# FRONT-UNIT.net
KiCad netlist of a schematic drawn in Altium Designer
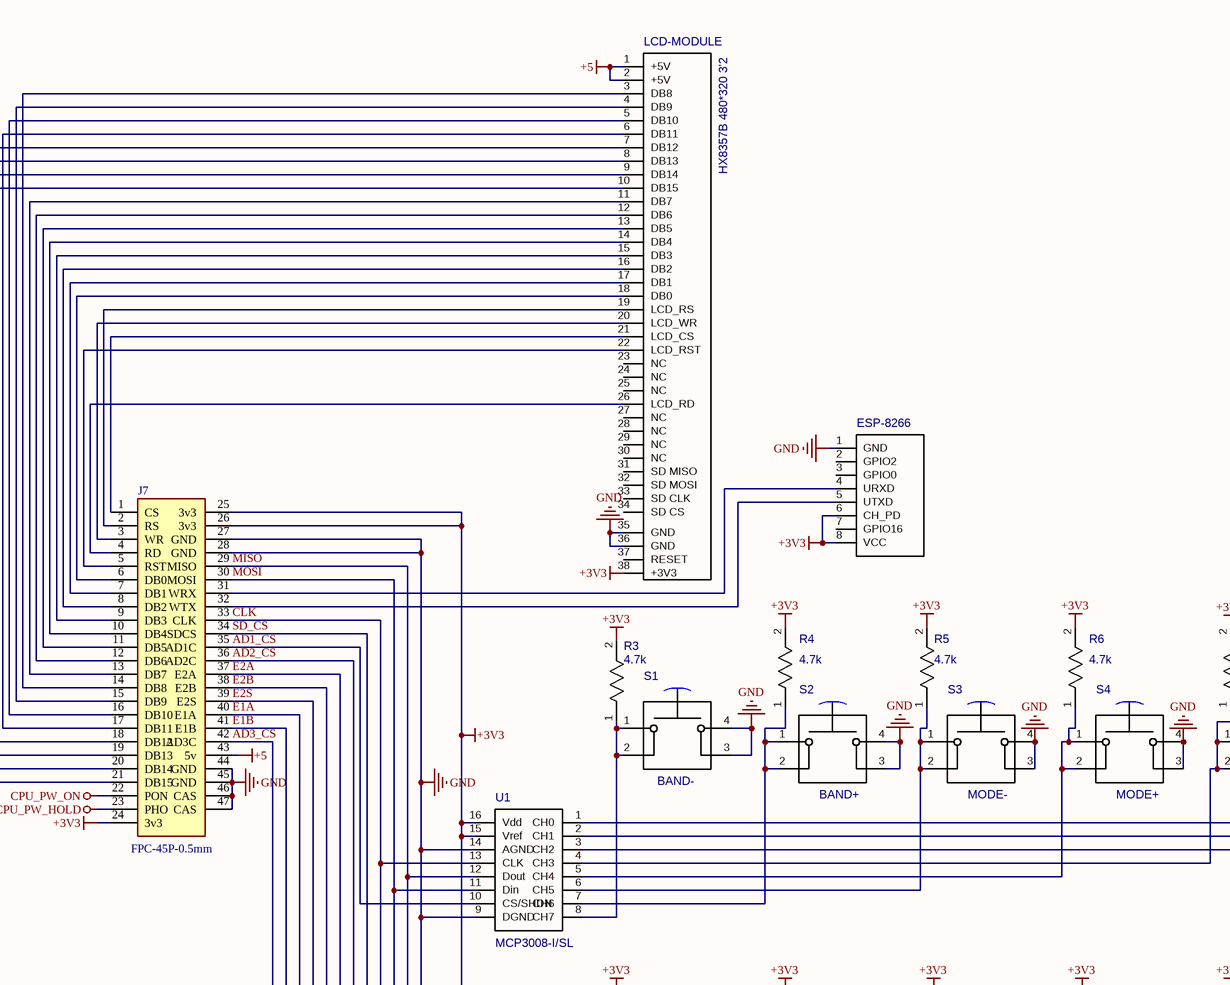
[diagram p0: FRONT-UNIT.SchDoc, top left]
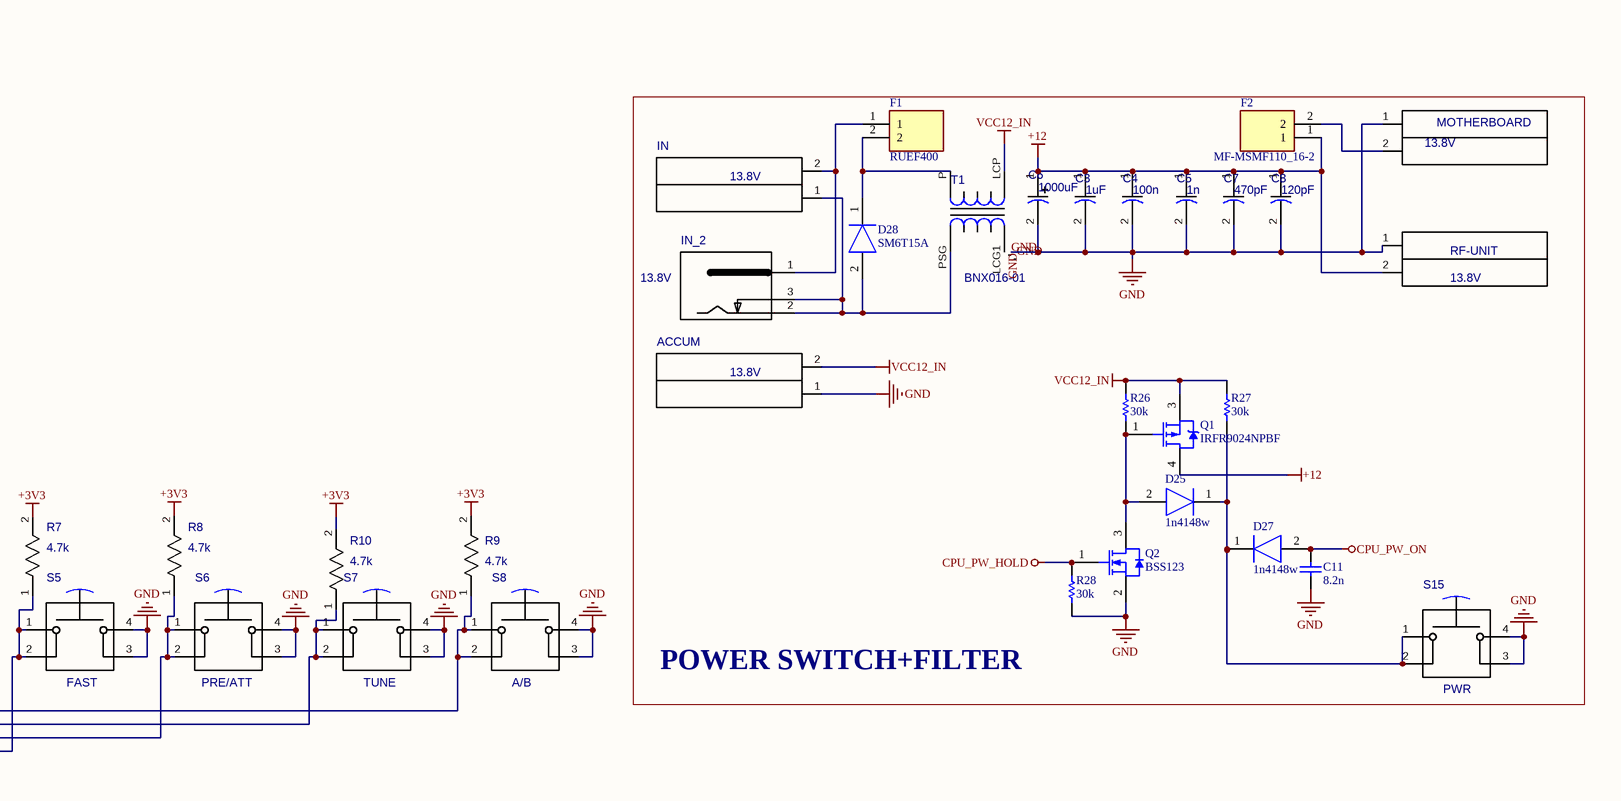
[diagram p1: FRONT-UNIT.SchDoc, top right]
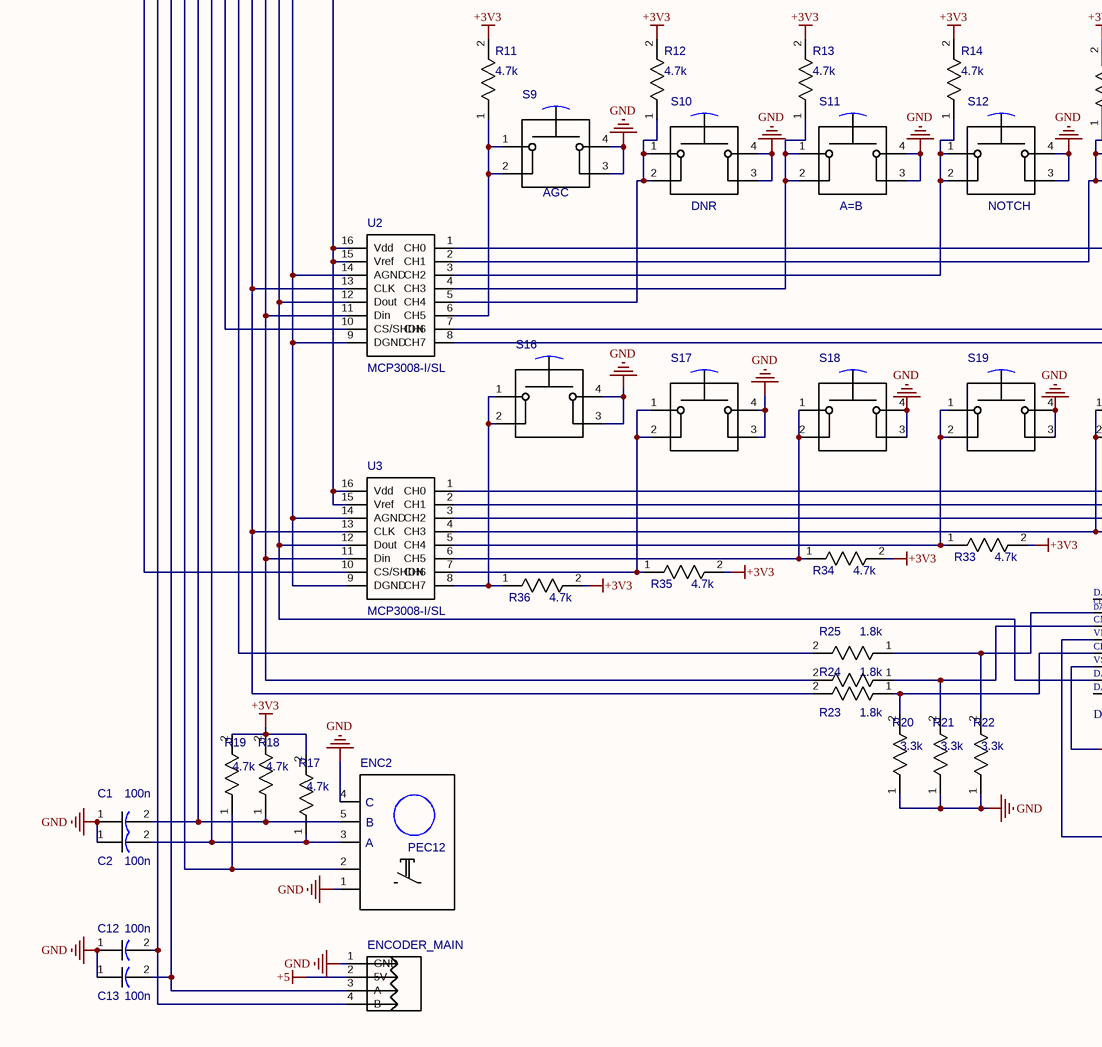
[diagram p2: FRONT-UNIT.SchDoc, bottom left]
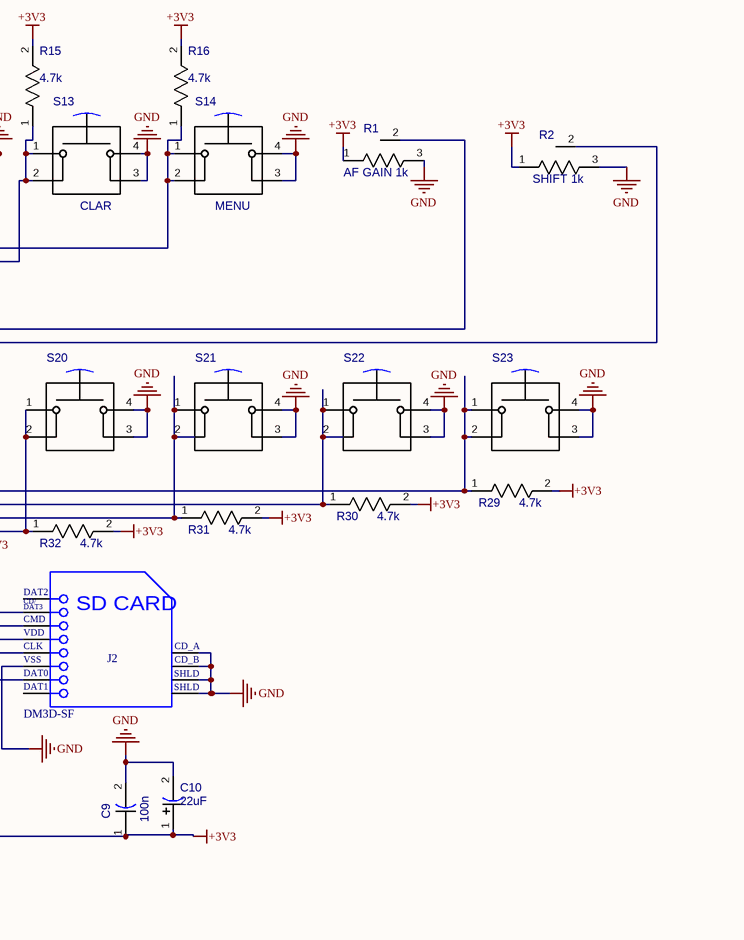
[diagram p3: FRONT-UNIT.SchDoc, bottom right]

(export (version "E")
  (design (tool "Eeschema 10.0.6"))
  (components
    (comp (ref "ACCUM")
      (value "13.8V")
      (footprint "JX2")
      (description "JX2")
      (libsource (lib "*") (part "JX2"))
    )
    (comp (ref "C1")
      (value "100n")
      (footprint "CAP_0805")
      (description "CAP_0805")
      (libsource (lib "*") (part "CAP_0805"))
    )
    (comp (ref "C2")
      (value "100n")
      (footprint "CAP_0805")
      (description "CAP_0805")
      (libsource (lib "*") (part "CAP_0805"))
    )
    (comp (ref "C3")
      (value "1uF")
      (footprint "CAP_1206")
      (description "CAP_1206")
      (libsource (lib "*") (part "CAP_1206"))
    )
    (comp (ref "C4")
      (value "100n")
      (footprint "CAP_1206")
      (description "CAP_1206")
      (libsource (lib "*") (part "CAP_1206"))
    )
    (comp (ref "C5")
      (value "1n")
      (footprint "CAP_1206")
      (description "CAP_1206")
      (libsource (lib "*") (part "CAP_1206"))
    )
    (comp (ref "C6")
      (value "1000uF")
      (footprint "CAP250RP")
      (description "CAP250RP")
      (libsource (lib "*") (part "CAP250RP"))
    )
    (comp (ref "C7")
      (value "470pF")
      (footprint "CAP_1206")
      (description "CAP_1206")
      (libsource (lib "*") (part "CAP_1206"))
    )
    (comp (ref "C8")
      (value "120pF")
      (footprint "CAP_1206")
      (description "CAP_1206")
      (libsource (lib "*") (part "CAP_1206"))
    )
    (comp (ref "C9")
      (value "100n")
      (footprint "CAP_0805")
      (description "CAP_0805")
      (libsource (lib "*") (part "CAP_0805"))
    )
    (comp (ref "C10")
      (value "22uF")
      (footprint "EEEFC_sizeB")
      (description "EEEFC_sizeB")
      (libsource (lib "*") (part "EEEFC_sizeB"))
    )
    (comp (ref "C11")
      (value "8.2n")
      (footprint "CAPC2013X94X50LL20T25")
      (description "CAP_1206")
      (fields
        (field (name "MANUFACTURER") "AVX Interconnect / Elco")
        (field (name "PART NUMBER") "08055C822KAT2A")
      )
      (libsource (lib "Altium Content Vault") (part "CAP"))
    )
    (comp (ref "C12")
      (value "100n")
      (footprint "CAP_0805")
      (description "CAP_0805")
      (libsource (lib "*") (part "CAP_0805"))
    )
    (comp (ref "C13")
      (value "100n")
      (footprint "CAP_0805")
      (description "CAP_0805")
      (libsource (lib "*") (part "CAP_0805"))
    )
    (comp (ref "D25")
      (value "1n4148w")
      (footprint "SamacSys:SOD3716X135N")
      (description "Diode")
      (libsource (lib "*") (part "1n4148w"))
    )
    (comp (ref "D27")
      (value "1n4148w")
      (footprint "SamacSys:SOD3716X135N")
      (description "Diode")
      (libsource (lib "*") (part "1n4148w"))
    )
    (comp (ref "D28")
      (value "SM6T15A")
      (footprint "SamacSys:SMBJ36CATR")
      (description "Diode")
      (fields (field (name "MOUSER PART NUMBER") "511-SM6T15A") (field (name "RS PART NUMBER") "4864915P"))
      (libsource (lib "*") (part "SM6T15A"))
    )
    (comp (ref "ENC2") (value "PEC12") (footprint "PEC12") (libsource (lib "*") (part "PEC12")))
    (comp (ref "ENCODER_MAIN")
      (value "OPTICAL ENCODER")
      (footprint "644456-4")
      (libsource (lib "*") (part "644456-4"))
    )
    (comp (ref "ESP-8266")
      (value "ESP-01 ESP8266")
      (footprint "ESP-01 ESP8266")
      (libsource (lib "*") (part "ESP-01 ESP8266"))
    )
    (comp (ref "F1")
      (value "RUEF400")
      (footprint "SamacSys:RUEF400")
      (description "Fuse")
      (fields (field (name "MOUSER PART NUMBER") "650-RUEF400") (field (name "RS PART NUMBER") "5176837P"))
      (libsource (lib "*") (part "RUEF400"))
    )
    (comp (ref "F2")
      (value "MF-MSMF110_16-2")
      (footprint "SamacSys:FUSC4632X85N")
      (description "Fuse")
      (fields
        (field (name "MANUFACTURER_PART_NUMBER") "MF-MSMF110/16-2")
        (field (name "MOUSER PART NUMBER") "652-MF-MSMF110/16-2")
      )
      (libsource (lib "*") (part "MF-MSMF110_16-2"))
    )
    (comp (ref "IN") (value "13.8V") (footprint "JX2") (description "JX2") (libsource (lib "*") (part "JX2")))
    (comp (ref "IN_2")
      (value "13.8V")
      (footprint "PJ-050B")
      (description "PJ-050B")
      (libsource (lib "*") (part "PJ-050B"))
    )
    (comp (ref "J2")
      (value "DM3D-SF")
      (footprint "HIRO-DM3D-SF_V")
      (fields (field (name "MANUFACTURER") "Hirose Electric"))
      (libsource (lib "Altium Content Vault") (part "CN-SD-8-2SW-2S"))
    )
    (comp (ref "J7")
      (value "FPC-45P-0.5mm")
      (footprint "SamacSys:FH12S45S05SH60")
      (description "Connector")
      (fields
        (field (name "MANUFACTURER_PART_NUMBER") "FH12S-45S-0.5SH(55)")
        (field (name "MOUSER PART NUMBER") "798-FH12S-45S-05SH55")
      )
      (libsource (lib "*") (part "FH12S-45S-0.5SH_55_"))
    )
    (comp (ref "LCD-MODULE")
      (value "HX8357B 480*320 3'2")
      (footprint "LCD-MODULE-3.2-480-320")
      (description "LCD-MODULE_3'2_480х320")
      (libsource (lib "FRONT-UNIT") (part "LCD-MODULE_3'2_480х320"))
    )
    (comp (ref "MOTHERBOARD")
      (value "13.8V")
      (footprint "JX2")
      (description "JX2")
      (libsource (lib "*") (part "JX2"))
    )
    (comp (ref "Q1")
      (value "IRFR9024NPBF")
      (footprint "ONSC-DPAK-3-369C-01_V")
      (description "IRFR9024NPBF, Транзистор, Р-канал 55В 11А")
      (fields (field (name "MANUFACTURER") "On Semiconductor") (field (name "PARTNUMBER") "NTD2955G"))
      (libsource (lib "Altium Content Vault") (part "ONSC-PMOS-G1S3D4-3_B"))
    )
    (comp (ref "Q2")
      (value "BSS123")
      (footprint "FAIR-SOT23-3_V")
      (fields (field (name "MANUFACTURER") "Fairchild"))
      (libsource (lib "Altium Content Vault") (part "NEMOS-GSD-3"))
    )
    (comp (ref "R1")
      (value "AF GAIN 1k")
      (footprint "PTV09")
      (description "Adjustable Resistor PTV09")
      (fields (field (name "Comment") "ptv09a-4225f-b102"))
      (libsource (lib "*") (part "PTV09"))
    )
    (comp (ref "R2")
      (value "SHIFT 1k")
      (footprint "PTV09")
      (description "Adjustable Resistor PTV09")
      (fields (field (name "Comment") "ptv09a-4225f-b102"))
      (libsource (lib "*") (part "PTV09"))
    )
    (comp (ref "R3")
      (value "4.7k")
      (footprint "RES_0805")
      (description "RES_0805")
      (libsource (lib "*") (part "RES_0805"))
    )
    (comp (ref "R4")
      (value "4.7k")
      (footprint "RES_0805")
      (description "RES_0805")
      (libsource (lib "*") (part "RES_0805"))
    )
    (comp (ref "R5")
      (value "4.7k")
      (footprint "RES_0805")
      (description "RES_0805")
      (libsource (lib "*") (part "RES_0805"))
    )
    (comp (ref "R6")
      (value "4.7k")
      (footprint "RES_0805")
      (description "RES_0805")
      (libsource (lib "*") (part "RES_0805"))
    )
    (comp (ref "R7")
      (value "4.7k")
      (footprint "RES_0805")
      (description "RES_0805")
      (libsource (lib "*") (part "RES_0805"))
    )
    (comp (ref "R8")
      (value "4.7k")
      (footprint "RES_0805")
      (description "RES_0805")
      (libsource (lib "*") (part "RES_0805"))
    )
    (comp (ref "R9")
      (value "4.7k")
      (footprint "RES_0805")
      (description "RES_0805")
      (libsource (lib "*") (part "RES_0805"))
    )
    (comp (ref "R10")
      (value "4.7k")
      (footprint "RES_0805")
      (description "RES_0805")
      (libsource (lib "*") (part "RES_0805"))
    )
    (comp (ref "R11")
      (value "4.7k")
      (footprint "RES_0805")
      (description "RES_0805")
      (libsource (lib "*") (part "RES_0805"))
    )
    (comp (ref "R12")
      (value "4.7k")
      (footprint "RES_0805")
      (description "RES_0805")
      (libsource (lib "*") (part "RES_0805"))
    )
    (comp (ref "R13")
      (value "4.7k")
      (footprint "RES_0805")
      (description "RES_0805")
      (libsource (lib "*") (part "RES_0805"))
    )
    (comp (ref "R14")
      (value "4.7k")
      (footprint "RES_0805")
      (description "RES_0805")
      (libsource (lib "*") (part "RES_0805"))
    )
    (comp (ref "R15")
      (value "4.7k")
      (footprint "RES_0805")
      (description "RES_0805")
      (libsource (lib "*") (part "RES_0805"))
    )
    (comp (ref "R16")
      (value "4.7k")
      (footprint "RES_0805")
      (description "RES_0805")
      (libsource (lib "*") (part "RES_0805"))
    )
    (comp (ref "R17")
      (value "4.7k")
      (footprint "RES_0805")
      (description "RES_0805")
      (libsource (lib "*") (part "RES_0805"))
    )
    (comp (ref "R18")
      (value "4.7k")
      (footprint "RES_0805")
      (description "RES_0805")
      (libsource (lib "*") (part "RES_0805"))
    )
    (comp (ref "R19")
      (value "4.7k")
      (footprint "RES_0805")
      (description "RES_0805")
      (libsource (lib "*") (part "RES_0805"))
    )
    (comp (ref "R20")
      (value "3.3k")
      (footprint "RES_0805")
      (description "RES_0805")
      (libsource (lib "*") (part "RES_0805"))
    )
    (comp (ref "R21")
      (value "3.3k")
      (footprint "RES_0805")
      (description "RES_0805")
      (libsource (lib "*") (part "RES_0805"))
    )
    (comp (ref "R22")
      (value "3.3k")
      (footprint "RES_0805")
      (description "RES_0805")
      (libsource (lib "*") (part "RES_0805"))
    )
    (comp (ref "R23")
      (value "1.8k")
      (footprint "RES_0805")
      (description "RES_0805")
      (libsource (lib "*") (part "RES_0805"))
    )
    (comp (ref "R24")
      (value "1.8k")
      (footprint "RES_0805")
      (description "RES_0805")
      (libsource (lib "*") (part "RES_0805"))
    )
    (comp (ref "R25")
      (value "1.8k")
      (footprint "RES_0805")
      (description "RES_0805")
      (libsource (lib "*") (part "RES_0805"))
    )
    (comp (ref "R26")
      (value "30k")
      (footprint "RESC2013X60X40NL20T25")
      (description "RES_0805")
      (fields (field (name "MANUFACTURER") "Panasonic") (field (name "PART NUMBER") "ERA-6AEB303V"))
      (libsource (lib "Altium Content Vault") (part "RES"))
    )
    (comp (ref "R27")
      (value "30k")
      (footprint "RESC2013X60X40NL20T25")
      (description "RES_0805")
      (fields (field (name "MANUFACTURER") "Panasonic") (field (name "PART NUMBER") "ERA-6AEB303V"))
      (libsource (lib "Altium Content Vault") (part "RES"))
    )
    (comp (ref "R28")
      (value "30k")
      (footprint "RESC2013X60X40NL20T25")
      (description "RES_0805")
      (fields (field (name "MANUFACTURER") "Panasonic") (field (name "PART NUMBER") "ERA-6AEB303V"))
      (libsource (lib "Altium Content Vault") (part "RES"))
    )
    (comp (ref "R29")
      (value "4.7k")
      (footprint "RES_0805")
      (description "RES_0805")
      (libsource (lib "*") (part "RES_0805"))
    )
    (comp (ref "R30")
      (value "4.7k")
      (footprint "RES_0805")
      (description "RES_0805")
      (libsource (lib "*") (part "RES_0805"))
    )
    (comp (ref "R31")
      (value "4.7k")
      (footprint "RES_0805")
      (description "RES_0805")
      (libsource (lib "*") (part "RES_0805"))
    )
    (comp (ref "R32")
      (value "4.7k")
      (footprint "RES_0805")
      (description "RES_0805")
      (libsource (lib "*") (part "RES_0805"))
    )
    (comp (ref "R33")
      (value "4.7k")
      (footprint "RES_0805")
      (description "RES_0805")
      (libsource (lib "*") (part "RES_0805"))
    )
    (comp (ref "R34")
      (value "4.7k")
      (footprint "RES_0805")
      (description "RES_0805")
      (libsource (lib "*") (part "RES_0805"))
    )
    (comp (ref "R35")
      (value "4.7k")
      (footprint "RES_0805")
      (description "RES_0805")
      (libsource (lib "*") (part "RES_0805"))
    )
    (comp (ref "R36")
      (value "4.7k")
      (footprint "RES_0805")
      (description "RES_0805")
      (libsource (lib "*") (part "RES_0805"))
    )
    (comp (ref "RF-UNIT")
      (value "13.8V")
      (footprint "JX2")
      (description "JX2")
      (libsource (lib "*") (part "JX2"))
    )
    (comp (ref "S1")
      (value "BAND-")
      (footprint "PTS645SK50LFS")
      (description "PTS645SK50LFS")
      (libsource (lib "*") (part "PTS645SK50LFS"))
    )
    (comp (ref "S2")
      (value "BAND+")
      (footprint "PTS645SK50LFS")
      (description "PTS645SK50LFS")
      (libsource (lib "*") (part "PTS645SK50LFS"))
    )
    (comp (ref "S3")
      (value "MODE-")
      (footprint "PTS645SK50LFS")
      (description "PTS645SK50LFS")
      (libsource (lib "*") (part "PTS645SK50LFS"))
    )
    (comp (ref "S4")
      (value "MODE+")
      (footprint "PTS645SK50LFS")
      (description "PTS645SK50LFS")
      (libsource (lib "*") (part "PTS645SK50LFS"))
    )
    (comp (ref "S5")
      (value "FAST")
      (footprint "PTS645SK50LFS")
      (description "PTS645SK50LFS")
      (libsource (lib "*") (part "PTS645SK50LFS"))
    )
    (comp (ref "S6")
      (value "PRE/ATT")
      (footprint "PTS645SK50LFS")
      (description "PTS645SK50LFS")
      (libsource (lib "*") (part "PTS645SK50LFS"))
    )
    (comp (ref "S7")
      (value "TUNE")
      (footprint "PTS645SK50LFS")
      (description "PTS645SK50LFS")
      (libsource (lib "*") (part "PTS645SK50LFS"))
    )
    (comp (ref "S8")
      (value "A/B")
      (footprint "PTS645SK50LFS")
      (description "PTS645SK50LFS")
      (libsource (lib "*") (part "PTS645SK50LFS"))
    )
    (comp (ref "S9")
      (value "AGC")
      (footprint "PTS645SK50LFS")
      (description "PTS645SK50LFS")
      (libsource (lib "*") (part "PTS645SK50LFS"))
    )
    (comp (ref "S10")
      (value "DNR")
      (footprint "PTS645SK50LFS")
      (description "PTS645SK50LFS")
      (libsource (lib "*") (part "PTS645SK50LFS"))
    )
    (comp (ref "S11")
      (value "A=B")
      (footprint "PTS645SK50LFS")
      (description "PTS645SK50LFS")
      (libsource (lib "*") (part "PTS645SK50LFS"))
    )
    (comp (ref "S12")
      (value "NOTCH")
      (footprint "PTS645SK50LFS")
      (description "PTS645SK50LFS")
      (libsource (lib "*") (part "PTS645SK50LFS"))
    )
    (comp (ref "S13")
      (value "CLAR")
      (footprint "PTS645SK50LFS")
      (description "PTS645SK50LFS")
      (libsource (lib "*") (part "PTS645SK50LFS"))
    )
    (comp (ref "S14")
      (value "MENU")
      (footprint "PTS645SK50LFS")
      (description "PTS645SK50LFS")
      (libsource (lib "*") (part "PTS645SK50LFS"))
    )
    (comp (ref "S15")
      (value "PWR")
      (footprint "PTS645SK50LFS")
      (description "PTS645SK50LFS")
      (libsource (lib "*") (part "PTS645SK50LFS"))
    )
    (comp (ref "S16")
      (value "PTS645SK50LFS")
      (footprint "PTS645SK50LFS")
      (libsource (lib "*") (part "PTS645SK50LFS"))
    )
    (comp (ref "S17")
      (value "PTS645SK50LFS")
      (footprint "PTS645SK50LFS")
      (libsource (lib "*") (part "PTS645SK50LFS"))
    )
    (comp (ref "S18")
      (value "PTS645SK50LFS")
      (footprint "PTS645SK50LFS")
      (libsource (lib "*") (part "PTS645SK50LFS"))
    )
    (comp (ref "S19")
      (value "PTS645SK50LFS")
      (footprint "PTS645SK50LFS")
      (libsource (lib "*") (part "PTS645SK50LFS"))
    )
    (comp (ref "S20")
      (value "PTS645SK50LFS")
      (footprint "PTS645SK50LFS")
      (libsource (lib "*") (part "PTS645SK50LFS"))
    )
    (comp (ref "S21")
      (value "PTS645SK50LFS")
      (footprint "PTS645SK50LFS")
      (libsource (lib "*") (part "PTS645SK50LFS"))
    )
    (comp (ref "S22")
      (value "PTS645SK50LFS")
      (footprint "PTS645SK50LFS")
      (libsource (lib "*") (part "PTS645SK50LFS"))
    )
    (comp (ref "S23")
      (value "PTS645SK50LFS")
      (footprint "PTS645SK50LFS")
      (libsource (lib "*") (part "PTS645SK50LFS"))
    )
    (comp (ref "T1")
      (value "BNX016-01")
      (footprint "TRANSF_ICORE")
      (libsource (lib "*") (part "TRANSF_ICORE"))
    )
    (comp (ref "U1")
      (value "MCP3008-I/SL")
      (footprint "MCP3008-I/SL")
      (libsource (lib "*") (part "MCP3008-I/SL"))
    )
    (comp (ref "U2")
      (value "MCP3008-I/SL")
      (footprint "MCP3008-I/SL")
      (libsource (lib "*") (part "MCP3008-I/SL"))
    )
    (comp (ref "U3")
      (value "MCP3008-I/SL")
      (footprint "MCP3008-I/SL")
      (libsource (lib "*") (part "MCP3008-I/SL"))
    )
  )
  (nets
    (net (code "1") (name "+3V3") (class "Default")
      (node (ref "C10") (pin "1") (pinfunction "PLUS_1") (pintype "passive"))
      (node (ref "C9") (pin "1") (pinfunction "1_1") (pintype "passive"))
      (node (ref "ESP-8266") (pin "6") (pinfunction "CH_PD_6") (pintype "passive"))
      (node (ref "ESP-8266") (pin "8") (pinfunction "VCC_8") (pintype "passive"))
      (node (ref "J2") (pin "4") (pinfunction "VDD_4") (pintype "passive"))
      (node (ref "J7") (pin "24") (pinfunction "3v3_24") (pintype "passive"))
      (node (ref "J7") (pin "25") (pinfunction "3v3_25") (pintype "passive"))
      (node (ref "J7") (pin "26") (pinfunction "3v3_26") (pintype "passive"))
      (node (ref "LCD-MODULE") (pin "38") (pinfunction "+3V3_38") (pintype "passive"))
      (node (ref "R1") (pin "1") (pinfunction "CW_1") (pintype "passive"))
      (node (ref "R10") (pin "2") (pinfunction "2_2") (pintype "passive"))
      (node (ref "R11") (pin "2") (pinfunction "2_2") (pintype "passive"))
      (node (ref "R12") (pin "2") (pinfunction "2_2") (pintype "passive"))
      (node (ref "R13") (pin "2") (pinfunction "2_2") (pintype "passive"))
      (node (ref "R14") (pin "2") (pinfunction "2_2") (pintype "passive"))
      (node (ref "R15") (pin "2") (pinfunction "2_2") (pintype "passive"))
      (node (ref "R16") (pin "2") (pinfunction "2_2") (pintype "passive"))
      (node (ref "R17") (pin "2") (pinfunction "2_2") (pintype "passive"))
      (node (ref "R18") (pin "2") (pinfunction "2_2") (pintype "passive"))
      (node (ref "R19") (pin "2") (pinfunction "2_2") (pintype "passive"))
      (node (ref "R2") (pin "1") (pinfunction "CW_1") (pintype "passive"))
      (node (ref "R29") (pin "2") (pinfunction "2_2") (pintype "passive"))
      (node (ref "R3") (pin "2") (pinfunction "2_2") (pintype "passive"))
      (node (ref "R30") (pin "2") (pinfunction "2_2") (pintype "passive"))
      (node (ref "R31") (pin "2") (pinfunction "2_2") (pintype "passive"))
      (node (ref "R32") (pin "2") (pinfunction "2_2") (pintype "passive"))
      (node (ref "R33") (pin "2") (pinfunction "2_2") (pintype "passive"))
      (node (ref "R34") (pin "2") (pinfunction "2_2") (pintype "passive"))
      (node (ref "R35") (pin "2") (pinfunction "2_2") (pintype "passive"))
      (node (ref "R36") (pin "2") (pinfunction "2_2") (pintype "passive"))
      (node (ref "R4") (pin "2") (pinfunction "2_2") (pintype "passive"))
      (node (ref "R5") (pin "2") (pinfunction "2_2") (pintype "passive"))
      (node (ref "R6") (pin "2") (pinfunction "2_2") (pintype "passive"))
      (node (ref "R7") (pin "2") (pinfunction "2_2") (pintype "passive"))
      (node (ref "R8") (pin "2") (pinfunction "2_2") (pintype "passive"))
      (node (ref "R9") (pin "2") (pinfunction "2_2") (pintype "passive"))
      (node (ref "U1") (pin "15") (pinfunction "Vref_15") (pintype "passive"))
      (node (ref "U1") (pin "16") (pinfunction "Vdd_16") (pintype "passive"))
      (node (ref "U2") (pin "15") (pinfunction "Vref_15") (pintype "passive"))
      (node (ref "U2") (pin "16") (pinfunction "Vdd_16") (pintype "passive"))
      (node (ref "U3") (pin "15") (pinfunction "Vref_15") (pintype "passive"))
      (node (ref "U3") (pin "16") (pinfunction "Vdd_16") (pintype "passive"))
    )
    (net (code "2") (name "+5") (class "Default")
      (node (ref "ENCODER_MAIN") (pin "2") (pinfunction "5V_2") (pintype "passive"))
      (node (ref "J7") (pin "43") (pinfunction "5v_43") (pintype "passive"))
      (node (ref "LCD-MODULE") (pin "1") (pinfunction "+5V_1") (pintype "passive"))
      (node (ref "LCD-MODULE") (pin "2") (pinfunction "+5V_2") (pintype "passive"))
    )
    (net (code "3") (name "+12") (class "Default")
      (node (ref "C3") (pin "1") (pinfunction "1_1") (pintype "passive"))
      (node (ref "C4") (pin "1") (pinfunction "1_1") (pintype "passive"))
      (node (ref "C5") (pin "1") (pinfunction "1_1") (pintype "passive"))
      (node (ref "C6") (pin "1") (pinfunction "PLUS_1") (pintype "passive"))
      (node (ref "C7") (pin "1") (pinfunction "1_1") (pintype "passive"))
      (node (ref "C8") (pin "1") (pinfunction "1_1") (pintype "passive"))
      (node (ref "F2") (pin "1") (pinfunction "1_1") (pintype "passive"))
      (node (ref "Q1") (pin "4") (pinfunction "D_4") (pintype "passive"))
      (node (ref "RF-UNIT") (pin "2") (pinfunction "1_2") (pintype "passive"))
    )
    (net (code "4") (name "/AD1_CS") (class "Default")
      (node (ref "J7") (pin "35") (pinfunction "AD1C_35") (pintype "passive"))
      (node (ref "U1") (pin "10") (pinfunction "CS/SHDN_10") (pintype "passive"))
    )
    (net (code "5") (name "/AD2_CS") (class "Default")
      (node (ref "J7") (pin "36") (pinfunction "AD2C_36") (pintype "passive"))
      (node (ref "U2") (pin "10") (pinfunction "CS/SHDN_10") (pintype "passive"))
    )
    (net (code "6") (name "/AD3_CS") (class "Default")
      (node (ref "J7") (pin "42") (pinfunction "AD3C_42") (pintype "passive"))
      (node (ref "U3") (pin "10") (pinfunction "CS/SHDN_10") (pintype "passive"))
    )
    (net (code "7") (name "/CLK") (class "Default")
      (node (ref "J7") (pin "33") (pinfunction "CLK_33") (pintype "passive"))
      (node (ref "R23") (pin "2") (pinfunction "2_2") (pintype "passive"))
      (node (ref "U1") (pin "13") (pinfunction "CLK_13") (pintype "passive"))
      (node (ref "U2") (pin "13") (pinfunction "CLK_13") (pintype "passive"))
      (node (ref "U3") (pin "13") (pinfunction "CLK_13") (pintype "passive"))
    )
    (net (code "8") (name "/E1A") (class "Default")
      (node (ref "C13") (pin "2") (pinfunction "2_2") (pintype "passive"))
      (node (ref "ENCODER_MAIN") (pin "3") (pinfunction "A_3") (pintype "passive"))
      (node (ref "J7") (pin "40") (pinfunction "E1A_40") (pintype "passive"))
    )
    (net (code "9") (name "/E1B") (class "Default")
      (node (ref "C12") (pin "2") (pinfunction "2_2") (pintype "passive"))
      (node (ref "ENCODER_MAIN") (pin "4") (pinfunction "B_4") (pintype "passive"))
      (node (ref "J7") (pin "41") (pinfunction "E1B_41") (pintype "passive"))
    )
    (net (code "10") (name "/E2A") (class "Default")
      (node (ref "C2") (pin "2") (pinfunction "2_2") (pintype "passive"))
      (node (ref "ENC2") (pin "3") (pinfunction "A_3") (pintype "passive"))
      (node (ref "J7") (pin "37") (pinfunction "E2A_37") (pintype "passive"))
      (node (ref "R17") (pin "1") (pinfunction "1_1") (pintype "passive"))
    )
    (net (code "11") (name "/E2B") (class "Default")
      (node (ref "C1") (pin "2") (pinfunction "2_2") (pintype "passive"))
      (node (ref "ENC2") (pin "5") (pinfunction "B_5") (pintype "passive"))
      (node (ref "J7") (pin "38") (pinfunction "E2B_38") (pintype "passive"))
      (node (ref "R18") (pin "1") (pinfunction "1_1") (pintype "passive"))
    )
    (net (code "12") (name "/E2S") (class "Default")
      (node (ref "ENC2") (pin "2") (pinfunction "2_2") (pintype "passive"))
      (node (ref "J7") (pin "39") (pinfunction "E2S_39") (pintype "passive"))
      (node (ref "R19") (pin "1") (pinfunction "1_1") (pintype "passive"))
    )
    (net (code "13") (name "/MISO") (class "Default")
      (node (ref "J2") (pin "7") (pinfunction "DAT0_7") (pintype "passive"))
      (node (ref "J7") (pin "29") (pinfunction "MISO_29") (pintype "passive"))
      (node (ref "U1") (pin "12") (pinfunction "Dout_12") (pintype "passive"))
      (node (ref "U2") (pin "12") (pinfunction "Dout_12") (pintype "passive"))
      (node (ref "U3") (pin "12") (pinfunction "Dout_12") (pintype "passive"))
    )
    (net (code "14") (name "/MOSI") (class "Default")
      (node (ref "J7") (pin "30") (pinfunction "MOSI_30") (pintype "passive"))
      (node (ref "R24") (pin "2") (pinfunction "2_2") (pintype "passive"))
      (node (ref "U1") (pin "11") (pinfunction "Din_11") (pintype "passive"))
      (node (ref "U2") (pin "11") (pinfunction "Din_11") (pintype "passive"))
      (node (ref "U3") (pin "11") (pinfunction "Din_11") (pintype "passive"))
    )
    (net (code "15") (name "/SD_CS") (class "Default")
      (node (ref "J7") (pin "34") (pinfunction "SDCS_34") (pintype "passive"))
      (node (ref "R25") (pin "2") (pinfunction "2_2") (pintype "passive"))
    )
    (net (code "16") (name "CPU_PW_HOLD") (class "Default")
      (node (ref "J7") (pin "23") (pinfunction "PHO_23") (pintype "passive"))
      (node (ref "Q2") (pin "1") (pinfunction "G_1") (pintype "passive"))
      (node (ref "R28") (pin "2") (pinfunction "2_2") (pintype "passive"))
    )
    (net (code "17") (name "CPU_PW_ON") (class "Default")
      (node (ref "C11") (pin "2") (pinfunction "2_2") (pintype "passive"))
      (node (ref "D27") (pin "2") (pinfunction "A_2") (pintype "passive"))
      (node (ref "J7") (pin "22") (pinfunction "PON_22") (pintype "passive"))
    )
    (net (code "18") (name "GND") (class "Default")
      (node (ref "ACCUM") (pin "1") (pinfunction "2_1") (pintype "passive"))
      (node (ref "C1") (pin "1") (pinfunction "1_1") (pintype "passive"))
      (node (ref "C10") (pin "2") (pinfunction "MINUS_2") (pintype "passive"))
      (node (ref "C11") (pin "1") (pinfunction "1_1") (pintype "passive"))
      (node (ref "C12") (pin "1") (pinfunction "1_1") (pintype "passive"))
      (node (ref "C13") (pin "1") (pinfunction "1_1") (pintype "passive"))
      (node (ref "C2") (pin "1") (pinfunction "1_1") (pintype "passive"))
      (node (ref "C3") (pin "2") (pinfunction "2_2") (pintype "passive"))
      (node (ref "C4") (pin "2") (pinfunction "2_2") (pintype "passive"))
      (node (ref "C5") (pin "2") (pinfunction "2_2") (pintype "passive"))
      (node (ref "C6") (pin "2") (pinfunction "MINUS_2") (pintype "passive"))
      (node (ref "C7") (pin "2") (pinfunction "2_2") (pintype "passive"))
      (node (ref "C8") (pin "2") (pinfunction "2_2") (pintype "passive"))
      (node (ref "C9") (pin "2") (pinfunction "2_2") (pintype "passive"))
      (node (ref "ENC2") (pin "1") (pinfunction "1_1") (pintype "passive"))
      (node (ref "ENC2") (pin "4") (pinfunction "C_4") (pintype "passive"))
      (node (ref "ENCODER_MAIN") (pin "1") (pinfunction "GND_1") (pintype "passive"))
      (node (ref "ESP-8266") (pin "1") (pinfunction "GND_1") (pintype "passive"))
      (node (ref "J2") (pin "10") (pinfunction "CD_B_10") (pintype "passive"))
      (node (ref "J2") (pin "11") (pinfunction "SHLD1_11") (pintype "passive"))
      (node (ref "J2") (pin "12") (pinfunction "SHLD2_12") (pintype "passive"))
      (node (ref "J2") (pin "13") (pinfunction "SHLD3_13") (pintype "passive"))
      (node (ref "J2") (pin "14") (pinfunction "SHLD4_14") (pintype "passive"))
      (node (ref "J2") (pin "6") (pinfunction "VSS2_6") (pintype "passive"))
      (node (ref "J2") (pin "9") (pinfunction "CD_A_9") (pintype "passive"))
      (node (ref "J7") (pin "27") (pinfunction "GND_27") (pintype "passive"))
      (node (ref "J7") (pin "28") (pinfunction "GND_28") (pintype "passive"))
      (node (ref "J7") (pin "44") (pinfunction "GND_44") (pintype "passive"))
      (node (ref "J7") (pin "45") (pinfunction "GND_45") (pintype "passive"))
      (node (ref "J7") (pin "46") (pinfunction "CAS_46") (pintype "passive"))
      (node (ref "J7") (pin "47") (pinfunction "CAS_47") (pintype "passive"))
      (node (ref "LCD-MODULE") (pin "35") (pinfunction "GND_35") (pintype "passive"))
      (node (ref "LCD-MODULE") (pin "36") (pinfunction "GND_36") (pintype "passive"))
      (node (ref "MOTHERBOARD") (pin "1") (pinfunction "2_1") (pintype "passive"))
      (node (ref "Q2") (pin "2") (pinfunction "S_2") (pintype "passive"))
      (node (ref "R1") (pin "3") (pinfunction "CCW_3") (pintype "passive"))
      (node (ref "R2") (pin "3") (pinfunction "CCW_3") (pintype "passive"))
      (node (ref "R20") (pin "1") (pinfunction "1_1") (pintype "passive"))
      (node (ref "R21") (pin "1") (pinfunction "1_1") (pintype "passive"))
      (node (ref "R22") (pin "1") (pinfunction "1_1") (pintype "passive"))
      (node (ref "R28") (pin "1") (pinfunction "1_1") (pintype "passive"))
      (node (ref "RF-UNIT") (pin "1") (pinfunction "2_1") (pintype "passive"))
      (node (ref "S1") (pin "3") (pinfunction "B_3") (pintype "passive"))
      (node (ref "S1") (pin "4") (pinfunction "B_4") (pintype "passive"))
      (node (ref "S10") (pin "3") (pinfunction "B_3") (pintype "passive"))
      (node (ref "S10") (pin "4") (pinfunction "B_4") (pintype "passive"))
      (node (ref "S11") (pin "3") (pinfunction "B_3") (pintype "passive"))
      (node (ref "S11") (pin "4") (pinfunction "B_4") (pintype "passive"))
      (node (ref "S12") (pin "3") (pinfunction "B_3") (pintype "passive"))
      (node (ref "S12") (pin "4") (pinfunction "B_4") (pintype "passive"))
      (node (ref "S13") (pin "3") (pinfunction "B_3") (pintype "passive"))
      (node (ref "S13") (pin "4") (pinfunction "B_4") (pintype "passive"))
      (node (ref "S14") (pin "3") (pinfunction "B_3") (pintype "passive"))
      (node (ref "S14") (pin "4") (pinfunction "B_4") (pintype "passive"))
      (node (ref "S15") (pin "3") (pinfunction "B_3") (pintype "passive"))
      (node (ref "S15") (pin "4") (pinfunction "B_4") (pintype "passive"))
      (node (ref "S16") (pin "3") (pinfunction "B_3") (pintype "passive"))
      (node (ref "S16") (pin "4") (pinfunction "B_4") (pintype "passive"))
      (node (ref "S17") (pin "3") (pinfunction "B_3") (pintype "passive"))
      (node (ref "S17") (pin "4") (pinfunction "B_4") (pintype "passive"))
      (node (ref "S18") (pin "3") (pinfunction "B_3") (pintype "passive"))
      (node (ref "S18") (pin "4") (pinfunction "B_4") (pintype "passive"))
      (node (ref "S19") (pin "3") (pinfunction "B_3") (pintype "passive"))
      (node (ref "S19") (pin "4") (pinfunction "B_4") (pintype "passive"))
      (node (ref "S2") (pin "3") (pinfunction "B_3") (pintype "passive"))
      (node (ref "S2") (pin "4") (pinfunction "B_4") (pintype "passive"))
      (node (ref "S20") (pin "3") (pinfunction "B_3") (pintype "passive"))
      (node (ref "S20") (pin "4") (pinfunction "B_4") (pintype "passive"))
      (node (ref "S21") (pin "3") (pinfunction "B_3") (pintype "passive"))
      (node (ref "S21") (pin "4") (pinfunction "B_4") (pintype "passive"))
      (node (ref "S22") (pin "3") (pinfunction "B_3") (pintype "passive"))
      (node (ref "S22") (pin "4") (pinfunction "B_4") (pintype "passive"))
      (node (ref "S23") (pin "3") (pinfunction "B_3") (pintype "passive"))
      (node (ref "S23") (pin "4") (pinfunction "B_4") (pintype "passive"))
      (node (ref "S3") (pin "3") (pinfunction "B_3") (pintype "passive"))
      (node (ref "S3") (pin "4") (pinfunction "B_4") (pintype "passive"))
      (node (ref "S4") (pin "3") (pinfunction "B_3") (pintype "passive"))
      (node (ref "S4") (pin "4") (pinfunction "B_4") (pintype "passive"))
      (node (ref "S5") (pin "3") (pinfunction "B_3") (pintype "passive"))
      (node (ref "S5") (pin "4") (pinfunction "B_4") (pintype "passive"))
      (node (ref "S6") (pin "3") (pinfunction "B_3") (pintype "passive"))
      (node (ref "S6") (pin "4") (pinfunction "B_4") (pintype "passive"))
      (node (ref "S7") (pin "3") (pinfunction "B_3") (pintype "passive"))
      (node (ref "S7") (pin "4") (pinfunction "B_4") (pintype "passive"))
      (node (ref "S8") (pin "3") (pinfunction "B_3") (pintype "passive"))
      (node (ref "S8") (pin "4") (pinfunction "B_4") (pintype "passive"))
      (node (ref "S9") (pin "3") (pinfunction "B_3") (pintype "passive"))
      (node (ref "S9") (pin "4") (pinfunction "B_4") (pintype "passive"))
      (node (ref "T1") (pin "LCG1") (pinfunction "S2_LCG1") (pintype "passive"))
      (node (ref "T1") (pin "LCG2") (pinfunction "0_LCG2") (pintype "passive"))
      (node (ref "T1") (pin "LCG3") (pinfunction "0_LCG3") (pintype "passive"))
      (node (ref "U1") (pin "14") (pinfunction "AGND_14") (pintype "passive"))
      (node (ref "U1") (pin "9") (pinfunction "DGND_9") (pintype "passive"))
      (node (ref "U2") (pin "14") (pinfunction "AGND_14") (pintype "passive"))
      (node (ref "U2") (pin "9") (pinfunction "DGND_9") (pintype "passive"))
      (node (ref "U3") (pin "14") (pinfunction "AGND_14") (pintype "passive"))
      (node (ref "U3") (pin "9") (pinfunction "DGND_9") (pintype "passive"))
    )
    (net (code "19") (name "Net-(D25-A)") (class "Default")
      (node (ref "D25") (pin "2") (pinfunction "A_2") (pintype "passive"))
      (node (ref "Q1") (pin "1") (pinfunction "G_1") (pintype "passive"))
      (node (ref "Q2") (pin "3") (pinfunction "D_3") (pintype "passive"))
      (node (ref "R26") (pin "1") (pinfunction "1_1") (pintype "passive"))
    )
    (net (code "20") (name "Net-(D25-K)") (class "Default")
      (node (ref "D25") (pin "1") (pinfunction "K_1") (pintype "passive"))
      (node (ref "D27") (pin "1") (pinfunction "K_1") (pintype "passive"))
      (node (ref "R27") (pin "1") (pinfunction "1_1") (pintype "passive"))
      (node (ref "S15") (pin "1") (pinfunction "A_1") (pintype "passive"))
      (node (ref "S15") (pin "2") (pinfunction "A_2") (pintype "passive"))
    )
    (net (code "21") (name "Net-(D28-A)") (class "Default")
      (node (ref "D28") (pin "2") (pinfunction "A_2") (pintype "passive"))
      (node (ref "IN") (pin "1") (pinfunction "2_1") (pintype "passive"))
      (node (ref "IN_2") (pin "2") (pinfunction "2_2") (pintype "passive"))
      (node (ref "IN_2") (pin "3") (pinfunction "3_3") (pintype "passive"))
      (node (ref "T1") (pin "PSG") (pinfunction "S1_PSG") (pintype "passive"))
    )
    (net (code "22") (name "Net-(D28-K)") (class "Default")
      (node (ref "D28") (pin "1") (pinfunction "K_1") (pintype "passive"))
      (node (ref "F1") (pin "2") (pinfunction "2_2") (pintype "passive"))
      (node (ref "T1") (pin "P") (pinfunction "P1_P") (pintype "passive"))
    )
    (net (code "23") (name "Net-(ESP-8266-URXD)") (class "Default")
      (node (ref "ESP-8266") (pin "4") (pinfunction "URXD_4") (pintype "passive"))
      (node (ref "J7") (pin "31") (pinfunction "WRX_31") (pintype "passive"))
    )
    (net (code "24") (name "Net-(ESP-8266-UTXD)") (class "Default")
      (node (ref "ESP-8266") (pin "5") (pinfunction "UTXD_5") (pintype "passive"))
      (node (ref "J7") (pin "32") (pinfunction "WTX_32") (pintype "passive"))
    )
    (net (code "25") (name "Net-(IN-1)") (class "Default")
      (node (ref "F1") (pin "1") (pinfunction "1_1") (pintype "passive"))
      (node (ref "IN") (pin "2") (pinfunction "1_2") (pintype "passive"))
      (node (ref "IN_2") (pin "1") (pinfunction "1_1") (pintype "passive"))
    )
    (net (code "26") (name "Net-(J2-CLK)") (class "Default")
      (node (ref "J2") (pin "5") (pinfunction "CLK_5") (pintype "passive"))
      (node (ref "R20") (pin "2") (pinfunction "2_2") (pintype "passive"))
      (node (ref "R23") (pin "1") (pinfunction "1_1") (pintype "passive"))
    )
    (net (code "27") (name "Net-(J2-CMD)") (class "Default")
      (node (ref "J2") (pin "2") (pinfunction "CMD_2") (pintype "passive"))
      (node (ref "R22") (pin "2") (pinfunction "2_2") (pintype "passive"))
      (node (ref "R25") (pin "1") (pinfunction "1_1") (pintype "passive"))
    )
    (net (code "28") (name "Net-(J2-VSS1)") (class "Default")
      (node (ref "J2") (pin "3") (pinfunction "VSS1_3") (pintype "passive"))
      (node (ref "R21") (pin "2") (pinfunction "2_2") (pintype "passive"))
      (node (ref "R24") (pin "1") (pinfunction "1_1") (pintype "passive"))
    )
    (net (code "29") (name "Net-(J7-CS)") (class "Default")
      (node (ref "J7") (pin "1") (pinfunction "CS_1") (pintype "passive"))
      (node (ref "LCD-MODULE") (pin "21") (pinfunction "LCD_CS_21") (pintype "passive"))
    )
    (net (code "30") (name "Net-(J7-DB0)") (class "Default")
      (node (ref "J7") (pin "6") (pinfunction "DB0_6") (pintype "passive"))
      (node (ref "LCD-MODULE") (pin "18") (pinfunction "DB0_18") (pintype "passive"))
    )
    (net (code "31") (name "Net-(J7-DB1)") (class "Default")
      (node (ref "J7") (pin "7") (pinfunction "DB1_7") (pintype "passive"))
      (node (ref "LCD-MODULE") (pin "17") (pinfunction "DB1_17") (pintype "passive"))
    )
    (net (code "32") (name "Net-(J7-DB2)") (class "Default")
      (node (ref "J7") (pin "8") (pinfunction "DB2_8") (pintype "passive"))
      (node (ref "LCD-MODULE") (pin "16") (pinfunction "DB2_16") (pintype "passive"))
    )
    (net (code "33") (name "Net-(J7-DB3)") (class "Default")
      (node (ref "J7") (pin "9") (pinfunction "DB3_9") (pintype "passive"))
      (node (ref "LCD-MODULE") (pin "15") (pinfunction "DB3_15") (pintype "passive"))
    )
    (net (code "34") (name "Net-(J7-DB4)") (class "Default")
      (node (ref "J7") (pin "10") (pinfunction "DB4_10") (pintype "passive"))
      (node (ref "LCD-MODULE") (pin "14") (pinfunction "DB4_14") (pintype "passive"))
    )
    (net (code "35") (name "Net-(J7-DB5)") (class "Default")
      (node (ref "J7") (pin "11") (pinfunction "DB5_11") (pintype "passive"))
      (node (ref "LCD-MODULE") (pin "13") (pinfunction "DB5_13") (pintype "passive"))
    )
    (net (code "36") (name "Net-(J7-DB6)") (class "Default")
      (node (ref "J7") (pin "12") (pinfunction "DB6_12") (pintype "passive"))
      (node (ref "LCD-MODULE") (pin "12") (pinfunction "DB6_12") (pintype "passive"))
    )
    (net (code "37") (name "Net-(J7-DB7)") (class "Default")
      (node (ref "J7") (pin "13") (pinfunction "DB7_13") (pintype "passive"))
      (node (ref "LCD-MODULE") (pin "11") (pinfunction "DB7_11") (pintype "passive"))
    )
    (net (code "38") (name "Net-(J7-DB8)") (class "Default")
      (node (ref "J7") (pin "14") (pinfunction "DB8_14") (pintype "passive"))
      (node (ref "LCD-MODULE") (pin "3") (pinfunction "DB8_3") (pintype "passive"))
    )
    (net (code "39") (name "Net-(J7-DB9)") (class "Default")
      (node (ref "J7") (pin "15") (pinfunction "DB9_15") (pintype "passive"))
      (node (ref "LCD-MODULE") (pin "4") (pinfunction "DB9_4") (pintype "passive"))
    )
    (net (code "40") (name "Net-(J7-DB10)") (class "Default")
      (node (ref "J7") (pin "16") (pinfunction "DB10_16") (pintype "passive"))
      (node (ref "LCD-MODULE") (pin "5") (pinfunction "DB10_5") (pintype "passive"))
    )
    (net (code "41") (name "Net-(J7-DB11)") (class "Default")
      (node (ref "J7") (pin "17") (pinfunction "DB11_17") (pintype "passive"))
      (node (ref "LCD-MODULE") (pin "6") (pinfunction "DB11_6") (pintype "passive"))
    )
    (net (code "42") (name "Net-(J7-DB12)") (class "Default")
      (node (ref "J7") (pin "18") (pinfunction "DB12_18") (pintype "passive"))
      (node (ref "LCD-MODULE") (pin "7") (pinfunction "DB12_7") (pintype "passive"))
    )
    (net (code "43") (name "Net-(J7-DB13)") (class "Default")
      (node (ref "J7") (pin "19") (pinfunction "DB13_19") (pintype "passive"))
      (node (ref "LCD-MODULE") (pin "8") (pinfunction "DB13_8") (pintype "passive"))
    )
    (net (code "44") (name "Net-(J7-DB14)") (class "Default")
      (node (ref "J7") (pin "20") (pinfunction "DB14_20") (pintype "passive"))
      (node (ref "LCD-MODULE") (pin "9") (pinfunction "DB14_9") (pintype "passive"))
    )
    (net (code "45") (name "Net-(J7-DB15)") (class "Default")
      (node (ref "J7") (pin "21") (pinfunction "DB15_21") (pintype "passive"))
      (node (ref "LCD-MODULE") (pin "10") (pinfunction "DB15_10") (pintype "passive"))
    )
    (net (code "46") (name "Net-(J7-RD)") (class "Default")
      (node (ref "J7") (pin "4") (pinfunction "RD_4") (pintype "passive"))
      (node (ref "LCD-MODULE") (pin "26") (pinfunction "LCD_RD_26") (pintype "passive"))
    )
    (net (code "47") (name "Net-(J7-RS)") (class "Default")
      (node (ref "J7") (pin "2") (pinfunction "RS_2") (pintype "passive"))
      (node (ref "LCD-MODULE") (pin "19") (pinfunction "LCD_RS_19") (pintype "passive"))
    )
    (net (code "48") (name "Net-(J7-RST)") (class "Default")
      (node (ref "J7") (pin "5") (pinfunction "RST_5") (pintype "passive"))
      (node (ref "LCD-MODULE") (pin "22") (pinfunction "LCD_RST_22") (pintype "passive"))
    )
    (net (code "49") (name "Net-(J7-WR)") (class "Default")
      (node (ref "J7") (pin "3") (pinfunction "WR_3") (pintype "passive"))
      (node (ref "LCD-MODULE") (pin "20") (pinfunction "LCD_WR_20") (pintype "passive"))
    )
    (net (code "50") (name "Net-(MOTHERBOARD-1)") (class "Default")
      (node (ref "F2") (pin "2") (pinfunction "2_2") (pintype "passive"))
      (node (ref "MOTHERBOARD") (pin "2") (pinfunction "1_2") (pintype "passive"))
    )
    (net (code "51") (name "Net-(R1-W)") (class "Default")
      (node (ref "R1") (pin "2") (pinfunction "W_2") (pintype "passive"))
      (node (ref "U2") (pin "7") (pinfunction "CH6_7") (pintype "passive"))
    )
    (net (code "52") (name "Net-(R2-W)") (class "Default")
      (node (ref "R2") (pin "2") (pinfunction "W_2") (pintype "passive"))
      (node (ref "U2") (pin "8") (pinfunction "CH7_8") (pintype "passive"))
    )
    (net (code "53") (name "Net-(U1-CH0)") (class "Default")
      (node (ref "R9") (pin "1") (pinfunction "1_1") (pintype "passive"))
      (node (ref "S8") (pin "1") (pinfunction "A_1") (pintype "passive"))
      (node (ref "S8") (pin "2") (pinfunction "A_2") (pintype "passive"))
      (node (ref "U1") (pin "1") (pinfunction "CH0_1") (pintype "passive"))
    )
    (net (code "54") (name "Net-(U1-CH1)") (class "Default")
      (node (ref "R10") (pin "1") (pinfunction "1_1") (pintype "passive"))
      (node (ref "S7") (pin "1") (pinfunction "A_1") (pintype "passive"))
      (node (ref "S7") (pin "2") (pinfunction "A_2") (pintype "passive"))
      (node (ref "U1") (pin "2") (pinfunction "CH1_2") (pintype "passive"))
    )
    (net (code "55") (name "Net-(U1-CH2)") (class "Default")
      (node (ref "R8") (pin "1") (pinfunction "1_1") (pintype "passive"))
      (node (ref "S6") (pin "1") (pinfunction "A_1") (pintype "passive"))
      (node (ref "S6") (pin "2") (pinfunction "A_2") (pintype "passive"))
      (node (ref "U1") (pin "3") (pinfunction "CH2_3") (pintype "passive"))
    )
    (net (code "56") (name "Net-(U1-CH3)") (class "Default")
      (node (ref "R7") (pin "1") (pinfunction "1_1") (pintype "passive"))
      (node (ref "S5") (pin "1") (pinfunction "A_1") (pintype "passive"))
      (node (ref "S5") (pin "2") (pinfunction "A_2") (pintype "passive"))
      (node (ref "U1") (pin "4") (pinfunction "CH3_4") (pintype "passive"))
    )
    (net (code "57") (name "Net-(U1-CH4)") (class "Default")
      (node (ref "R6") (pin "1") (pinfunction "1_1") (pintype "passive"))
      (node (ref "S4") (pin "1") (pinfunction "A_1") (pintype "passive"))
      (node (ref "S4") (pin "2") (pinfunction "A_2") (pintype "passive"))
      (node (ref "U1") (pin "5") (pinfunction "CH4_5") (pintype "passive"))
    )
    (net (code "58") (name "Net-(U1-CH5)") (class "Default")
      (node (ref "R5") (pin "1") (pinfunction "1_1") (pintype "passive"))
      (node (ref "S3") (pin "1") (pinfunction "A_1") (pintype "passive"))
      (node (ref "S3") (pin "2") (pinfunction "A_2") (pintype "passive"))
      (node (ref "U1") (pin "6") (pinfunction "CH5_6") (pintype "passive"))
    )
    (net (code "59") (name "Net-(U1-CH6)") (class "Default")
      (node (ref "R4") (pin "1") (pinfunction "1_1") (pintype "passive"))
      (node (ref "S2") (pin "1") (pinfunction "A_1") (pintype "passive"))
      (node (ref "S2") (pin "2") (pinfunction "A_2") (pintype "passive"))
      (node (ref "U1") (pin "7") (pinfunction "CH6_7") (pintype "passive"))
    )
    (net (code "60") (name "Net-(U1-CH7)") (class "Default")
      (node (ref "R3") (pin "1") (pinfunction "1_1") (pintype "passive"))
      (node (ref "S1") (pin "1") (pinfunction "A_1") (pintype "passive"))
      (node (ref "S1") (pin "2") (pinfunction "A_2") (pintype "passive"))
      (node (ref "U1") (pin "8") (pinfunction "CH7_8") (pintype "passive"))
    )
    (net (code "61") (name "Net-(U2-CH0)") (class "Default")
      (node (ref "R16") (pin "1") (pinfunction "1_1") (pintype "passive"))
      (node (ref "S14") (pin "1") (pinfunction "A_1") (pintype "passive"))
      (node (ref "S14") (pin "2") (pinfunction "A_2") (pintype "passive"))
      (node (ref "U2") (pin "1") (pinfunction "CH0_1") (pintype "passive"))
    )
    (net (code "62") (name "Net-(U2-CH1)") (class "Default")
      (node (ref "R15") (pin "1") (pinfunction "1_1") (pintype "passive"))
      (node (ref "S13") (pin "1") (pinfunction "A_1") (pintype "passive"))
      (node (ref "S13") (pin "2") (pinfunction "A_2") (pintype "passive"))
      (node (ref "U2") (pin "2") (pinfunction "CH1_2") (pintype "passive"))
    )
    (net (code "63") (name "Net-(U2-CH2)") (class "Default")
      (node (ref "R14") (pin "1") (pinfunction "1_1") (pintype "passive"))
      (node (ref "S12") (pin "1") (pinfunction "A_1") (pintype "passive"))
      (node (ref "S12") (pin "2") (pinfunction "A_2") (pintype "passive"))
      (node (ref "U2") (pin "3") (pinfunction "CH2_3") (pintype "passive"))
    )
    (net (code "64") (name "Net-(U2-CH3)") (class "Default")
      (node (ref "R13") (pin "1") (pinfunction "1_1") (pintype "passive"))
      (node (ref "S11") (pin "1") (pinfunction "A_1") (pintype "passive"))
      (node (ref "S11") (pin "2") (pinfunction "A_2") (pintype "passive"))
      (node (ref "U2") (pin "4") (pinfunction "CH3_4") (pintype "passive"))
    )
    (net (code "65") (name "Net-(U2-CH4)") (class "Default")
      (node (ref "R12") (pin "1") (pinfunction "1_1") (pintype "passive"))
      (node (ref "S10") (pin "1") (pinfunction "A_1") (pintype "passive"))
      (node (ref "S10") (pin "2") (pinfunction "A_2") (pintype "passive"))
      (node (ref "U2") (pin "5") (pinfunction "CH4_5") (pintype "passive"))
    )
    (net (code "66") (name "Net-(U2-CH5)") (class "Default")
      (node (ref "R11") (pin "1") (pinfunction "1_1") (pintype "passive"))
      (node (ref "S9") (pin "1") (pinfunction "A_1") (pintype "passive"))
      (node (ref "S9") (pin "2") (pinfunction "A_2") (pintype "passive"))
      (node (ref "U2") (pin "6") (pinfunction "CH5_6") (pintype "passive"))
    )
    (net (code "67") (name "Net-(U3-CH0)") (class "Default")
      (node (ref "R29") (pin "1") (pinfunction "1_1") (pintype "passive"))
      (node (ref "S23") (pin "1") (pinfunction "A_1") (pintype "passive"))
      (node (ref "S23") (pin "2") (pinfunction "A_2") (pintype "passive"))
      (node (ref "U3") (pin "1") (pinfunction "CH0_1") (pintype "passive"))
    )
    (net (code "68") (name "Net-(U3-CH1)") (class "Default")
      (node (ref "R30") (pin "1") (pinfunction "1_1") (pintype "passive"))
      (node (ref "S22") (pin "1") (pinfunction "A_1") (pintype "passive"))
      (node (ref "S22") (pin "2") (pinfunction "A_2") (pintype "passive"))
      (node (ref "U3") (pin "2") (pinfunction "CH1_2") (pintype "passive"))
    )
    (net (code "69") (name "Net-(U3-CH2)") (class "Default")
      (node (ref "R31") (pin "1") (pinfunction "1_1") (pintype "passive"))
      (node (ref "S21") (pin "1") (pinfunction "A_1") (pintype "passive"))
      (node (ref "S21") (pin "2") (pinfunction "A_2") (pintype "passive"))
      (node (ref "U3") (pin "3") (pinfunction "CH2_3") (pintype "passive"))
    )
    (net (code "70") (name "Net-(U3-CH3)") (class "Default")
      (node (ref "R32") (pin "1") (pinfunction "1_1") (pintype "passive"))
      (node (ref "S20") (pin "1") (pinfunction "A_1") (pintype "passive"))
      (node (ref "S20") (pin "2") (pinfunction "A_2") (pintype "passive"))
      (node (ref "U3") (pin "4") (pinfunction "CH3_4") (pintype "passive"))
    )
    (net (code "71") (name "Net-(U3-CH4)") (class "Default")
      (node (ref "R33") (pin "1") (pinfunction "1_1") (pintype "passive"))
      (node (ref "S19") (pin "1") (pinfunction "A_1") (pintype "passive"))
      (node (ref "S19") (pin "2") (pinfunction "A_2") (pintype "passive"))
      (node (ref "U3") (pin "5") (pinfunction "CH4_5") (pintype "passive"))
    )
    (net (code "72") (name "Net-(U3-CH5)") (class "Default")
      (node (ref "R34") (pin "1") (pinfunction "1_1") (pintype "passive"))
      (node (ref "S18") (pin "1") (pinfunction "A_1") (pintype "passive"))
      (node (ref "S18") (pin "2") (pinfunction "A_2") (pintype "passive"))
      (node (ref "U3") (pin "6") (pinfunction "CH5_6") (pintype "passive"))
    )
    (net (code "73") (name "Net-(U3-CH6)") (class "Default")
      (node (ref "R35") (pin "1") (pinfunction "1_1") (pintype "passive"))
      (node (ref "S17") (pin "1") (pinfunction "A_1") (pintype "passive"))
      (node (ref "S17") (pin "2") (pinfunction "A_2") (pintype "passive"))
      (node (ref "U3") (pin "7") (pinfunction "CH6_7") (pintype "passive"))
    )
    (net (code "74") (name "Net-(U3-CH7)") (class "Default")
      (node (ref "R36") (pin "1") (pinfunction "1_1") (pintype "passive"))
      (node (ref "S16") (pin "1") (pinfunction "A_1") (pintype "passive"))
      (node (ref "S16") (pin "2") (pinfunction "A_2") (pintype "passive"))
      (node (ref "U3") (pin "8") (pinfunction "CH7_8") (pintype "passive"))
    )
    (net (code "75") (name "VCC12_IN") (class "Default")
      (node (ref "ACCUM") (pin "2") (pinfunction "1_2") (pintype "passive"))
      (node (ref "Q1") (pin "3") (pinfunction "S_3") (pintype "passive"))
      (node (ref "R26") (pin "2") (pinfunction "2_2") (pintype "passive"))
      (node (ref "R27") (pin "2") (pinfunction "2_2") (pintype "passive"))
      (node (ref "T1") (pin "LCP") (pinfunction "P2_LCP") (pintype "passive"))
    )
    (net (code "76") (name "unconnected-(ESP-8266-GPIO0-Pad3)") (class "Default")
      (node (ref "ESP-8266") (pin "3") (pinfunction "GPIO0_3") (pintype "passive"))
    )
    (net (code "77") (name "unconnected-(ESP-8266-GPIO2-Pad2)") (class "Default")
      (node (ref "ESP-8266") (pin "2") (pinfunction "GPIO2_2") (pintype "passive"))
    )
    (net (code "78") (name "unconnected-(ESP-8266-GPIO16-Pad7)") (class "Default")
      (node (ref "ESP-8266") (pin "7") (pinfunction "GPIO16_7") (pintype "passive"))
    )
    (net (code "79") (name "unconnected-(J2-CD{slash}DAT3-Pad1)") (class "Default")
      (node (ref "J2") (pin "1") (pinfunction "CD/DAT3_1") (pintype "passive"))
    )
    (net (code "80") (name "unconnected-(J2-DAT1-Pad8)") (class "Default")
      (node (ref "J2") (pin "8") (pinfunction "DAT1_8") (pintype "passive"))
    )
    (net (code "81") (name "unconnected-(LCD-MODULE-NC-Pad23)") (class "Default")
      (node (ref "LCD-MODULE") (pin "23") (pinfunction "NC_23") (pintype "passive"))
    )
    (net (code "82") (name "unconnected-(LCD-MODULE-NC-Pad24)") (class "Default")
      (node (ref "LCD-MODULE") (pin "24") (pinfunction "NC_24") (pintype "passive"))
    )
    (net (code "83") (name "unconnected-(LCD-MODULE-NC-Pad25)") (class "Default")
      (node (ref "LCD-MODULE") (pin "25") (pinfunction "NC_25") (pintype "passive"))
    )
    (net (code "84") (name "unconnected-(LCD-MODULE-NC-Pad27)") (class "Default")
      (node (ref "LCD-MODULE") (pin "27") (pinfunction "NC_27") (pintype "passive"))
    )
    (net (code "85") (name "unconnected-(LCD-MODULE-NC-Pad28)") (class "Default")
      (node (ref "LCD-MODULE") (pin "28") (pinfunction "NC_28") (pintype "passive"))
    )
    (net (code "86") (name "unconnected-(LCD-MODULE-NC-Pad29)") (class "Default")
      (node (ref "LCD-MODULE") (pin "29") (pinfunction "NC_29") (pintype "passive"))
    )
    (net (code "87") (name "unconnected-(LCD-MODULE-NC-Pad30)") (class "Default")
      (node (ref "LCD-MODULE") (pin "30") (pinfunction "NC_30") (pintype "passive"))
    )
    (net (code "88") (name "unconnected-(LCD-MODULE-RESET-Pad37)") (class "Default")
      (node (ref "LCD-MODULE") (pin "37") (pinfunction "RESET_37") (pintype "passive"))
    )
    (net (code "89") (name "unconnected-(LCD-MODULE-SD_CLK-Pad33)") (class "Default")
      (node (ref "LCD-MODULE") (pin "33") (pinfunction "SD_CLK_33") (pintype "passive"))
    )
    (net (code "90") (name "unconnected-(LCD-MODULE-SD_CS-Pad34)") (class "Default")
      (node (ref "LCD-MODULE") (pin "34") (pinfunction "SD_CS_34") (pintype "passive"))
    )
    (net (code "91") (name "unconnected-(LCD-MODULE-SD_MISO-Pad31)") (class "Default")
      (node (ref "LCD-MODULE") (pin "31") (pinfunction "SD_MISO_31") (pintype "passive"))
    )
    (net (code "92") (name "unconnected-(LCD-MODULE-SD_MOSI-Pad32)") (class "Default")
      (node (ref "LCD-MODULE") (pin "32") (pinfunction "SD_MOSI_32") (pintype "passive"))
    )
  )
)
